# Boron485.net
KiCad netlist of a schematic drawn in EAGLE
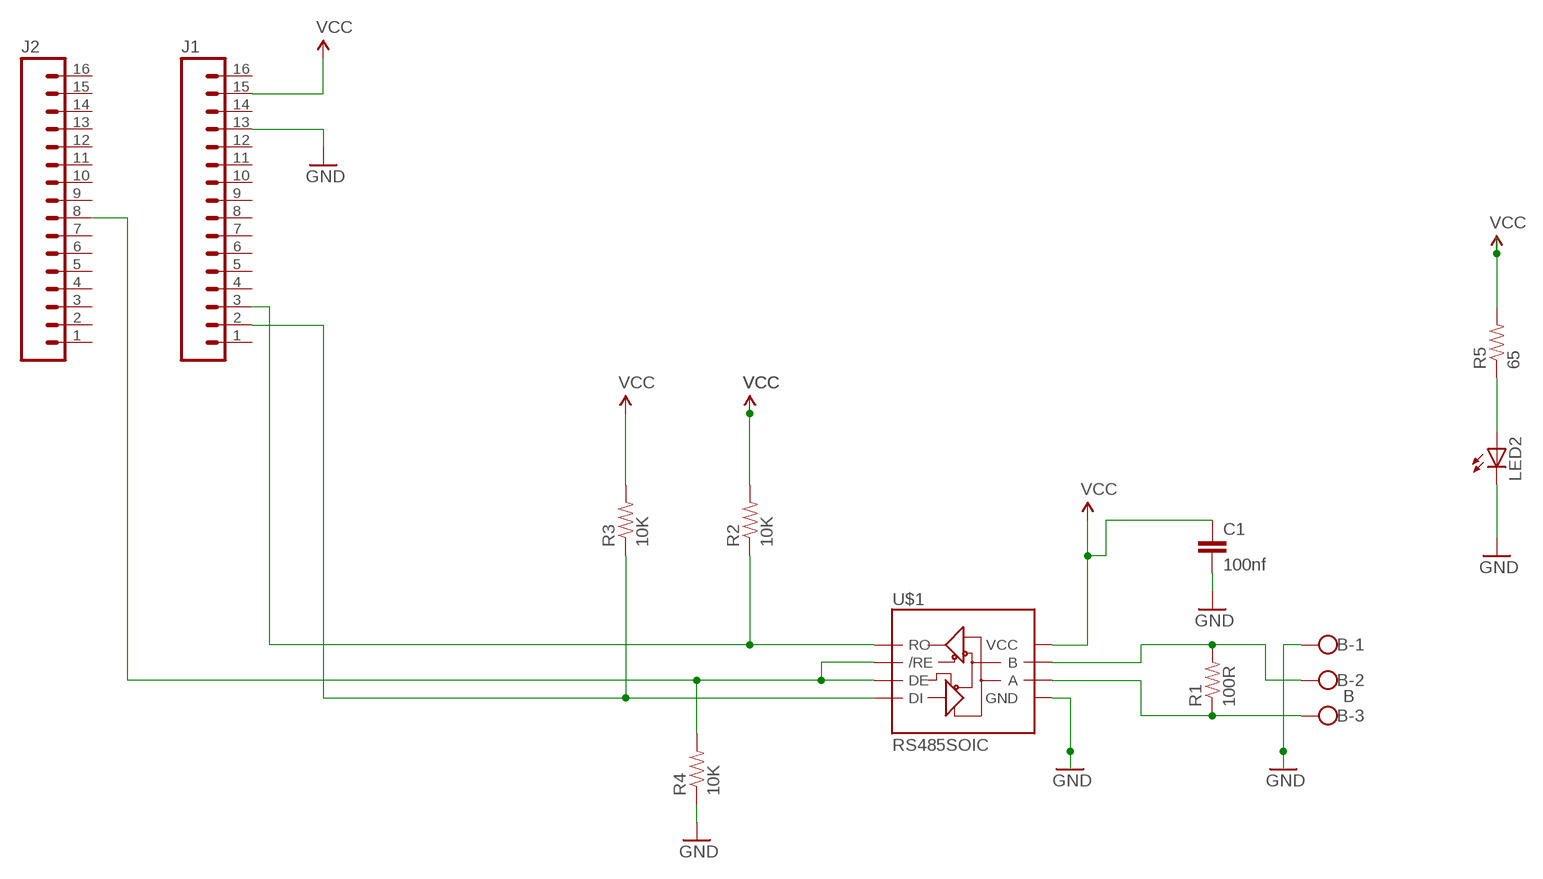
[diagram p0: schematic, sheet 1]

(export (version "E")
  (design (tool "Eeschema 10.0.6"))
  (components
    (comp (ref "B")
      (value "B")
      (footprint "eagle-import:W237-103")
      (fields (field (name "MPN") "237-103"))
      (libsource (lib "eagle-import") (part "W237-103"))
    )
    (comp (ref "C1")
      (value "100nf")
      (footprint "eagle-import:C0603")
      (libsource (lib "eagle-import") (part "C-EUC0603"))
    )
    (comp (ref "J1")
      (value "M16PTH")
      (footprint "eagle-import:1X16")
      (libsource (lib "eagle-import") (part "M16PTH"))
    )
    (comp (ref "J2")
      (value "M16PTH")
      (footprint "eagle-import:1X16")
      (libsource (lib "eagle-import") (part "M16PTH"))
    )
    (comp (ref "LED2")
      (value "LED_E")
      (footprint "eagle-import:LED_1206")
      (libsource (lib "eagle-import") (part "LED_E"))
    )
    (comp (ref "R1")
      (value "100R")
      (footprint "eagle-import:0603-RES")
      (libsource (lib "eagle-import") (part "RESISTOR0603-RES"))
    )
    (comp (ref "R2")
      (value "10K")
      (footprint "eagle-import:0603-RES")
      (libsource (lib "eagle-import") (part "RESISTOR0603-RES"))
    )
    (comp (ref "R3")
      (value "10K")
      (footprint "eagle-import:0603-RES")
      (libsource (lib "eagle-import") (part "RESISTOR0603-RES"))
    )
    (comp (ref "R4")
      (value "10K")
      (footprint "eagle-import:0603-RES")
      (libsource (lib "eagle-import") (part "RESISTOR0603-RES"))
    )
    (comp (ref "R5")
      (value "65")
      (footprint "eagle-import:0603-RES")
      (libsource (lib "eagle-import") (part "RESISTOR0603-RES"))
    )
    (comp (ref "U$1")
      (value "RS485SOIC")
      (footprint "eagle-import:SO08")
      (libsource (lib "eagle-import") (part "RS485SOIC"))
    )
  )
  (nets
    (net (code "1") (name "GND") (class "Default")
      (node (ref "B") (pin "1") (pinfunction "KL_1") (pintype "passive"))
      (node (ref "C1") (pin "2") (pinfunction "2_2") (pintype "passive"))
      (node (ref "J1") (pin "13") (pinfunction "13_13") (pintype "passive"))
      (node (ref "LED2") (pin "C") (pinfunction "C_C") (pintype "passive"))
      (node (ref "R4") (pin "1") (pinfunction "1_1") (pintype "passive"))
      (node (ref "U$1") (pin "5") (pinfunction "GND_5") (pintype "bidirectional"))
    )
    (net (code "2") (name "Net-(BB-KL)") (class "Default")
      (node (ref "B") (pin "2") (pinfunction "KL_2") (pintype "passive"))
      (node (ref "R1") (pin "2") (pinfunction "2_2") (pintype "passive"))
      (node (ref "U$1") (pin "7") (pinfunction "B_7") (pintype "bidirectional"))
    )
    (net (code "3") (name "Net-(BC-KL)") (class "Default")
      (node (ref "B") (pin "3") (pinfunction "KL_3") (pintype "passive"))
      (node (ref "R1") (pin "1") (pinfunction "1_1") (pintype "passive"))
      (node (ref "U$1") (pin "6") (pinfunction "A_6") (pintype "bidirectional"))
    )
    (net (code "4") (name "Net-(LED2-PadA)") (class "Default")
      (node (ref "LED2") (pin "A") (pinfunction "A_A") (pintype "passive"))
      (node (ref "R5") (pin "1") (pinfunction "1_1") (pintype "passive"))
    )
    (net (code "5") (name "Net-(U$1-DE)") (class "Default")
      (node (ref "J2") (pin "8") (pinfunction "8_8") (pintype "passive"))
      (node (ref "R4") (pin "2") (pinfunction "2_2") (pintype "passive"))
      (node (ref "U$1") (pin "2") (pinfunction "/RE_2") (pintype "bidirectional"))
      (node (ref "U$1") (pin "3") (pinfunction "DE_3") (pintype "bidirectional"))
    )
    (net (code "6") (name "Net-(U$1-DI)") (class "Default")
      (node (ref "J1") (pin "2") (pinfunction "2_2") (pintype "passive"))
      (node (ref "R3") (pin "1") (pinfunction "1_1") (pintype "passive"))
      (node (ref "U$1") (pin "4") (pinfunction "DI_4") (pintype "bidirectional"))
    )
    (net (code "7") (name "Net-(U$1-RO)") (class "Default")
      (node (ref "J1") (pin "3") (pinfunction "3_3") (pintype "passive"))
      (node (ref "R2") (pin "1") (pinfunction "1_1") (pintype "passive"))
      (node (ref "U$1") (pin "1") (pinfunction "RO_1") (pintype "bidirectional"))
    )
    (net (code "8") (name "VCC") (class "Default")
      (node (ref "C1") (pin "1") (pinfunction "1_1") (pintype "passive"))
      (node (ref "J1") (pin "15") (pinfunction "15_15") (pintype "passive"))
      (node (ref "R2") (pin "2") (pinfunction "2_2") (pintype "passive"))
      (node (ref "R3") (pin "2") (pinfunction "2_2") (pintype "passive"))
      (node (ref "R5") (pin "2") (pinfunction "2_2") (pintype "passive"))
      (node (ref "U$1") (pin "8") (pinfunction "VCC_8") (pintype "bidirectional"))
    )
    (net (code "9") (name "unconnected-(J1-Pad1)") (class "Default")
      (node (ref "J1") (pin "1") (pinfunction "1_1") (pintype "passive"))
    )
    (net (code "10") (name "unconnected-(J1-Pad4)") (class "Default")
      (node (ref "J1") (pin "4") (pinfunction "4_4") (pintype "passive"))
    )
    (net (code "11") (name "unconnected-(J1-Pad5)") (class "Default")
      (node (ref "J1") (pin "5") (pinfunction "5_5") (pintype "passive"))
    )
    (net (code "12") (name "unconnected-(J1-Pad6)") (class "Default")
      (node (ref "J1") (pin "6") (pinfunction "6_6") (pintype "passive"))
    )
    (net (code "13") (name "unconnected-(J1-Pad7)") (class "Default")
      (node (ref "J1") (pin "7") (pinfunction "7_7") (pintype "passive"))
    )
    (net (code "14") (name "unconnected-(J1-Pad8)") (class "Default")
      (node (ref "J1") (pin "8") (pinfunction "8_8") (pintype "passive"))
    )
    (net (code "15") (name "unconnected-(J1-Pad9)") (class "Default")
      (node (ref "J1") (pin "9") (pinfunction "9_9") (pintype "passive"))
    )
    (net (code "16") (name "unconnected-(J1-Pad10)") (class "Default")
      (node (ref "J1") (pin "10") (pinfunction "10_10") (pintype "passive"))
    )
    (net (code "17") (name "unconnected-(J1-Pad11)") (class "Default")
      (node (ref "J1") (pin "11") (pinfunction "11_11") (pintype "passive"))
    )
    (net (code "18") (name "unconnected-(J1-Pad12)") (class "Default")
      (node (ref "J1") (pin "12") (pinfunction "12_12") (pintype "passive"))
    )
    (net (code "19") (name "unconnected-(J1-Pad14)") (class "Default")
      (node (ref "J1") (pin "14") (pinfunction "14_14") (pintype "passive"))
    )
    (net (code "20") (name "unconnected-(J1-Pad16)") (class "Default")
      (node (ref "J1") (pin "16") (pinfunction "16_16") (pintype "passive"))
    )
    (net (code "21") (name "unconnected-(J2-Pad1)") (class "Default")
      (node (ref "J2") (pin "1") (pinfunction "1_1") (pintype "passive"))
    )
    (net (code "22") (name "unconnected-(J2-Pad2)") (class "Default")
      (node (ref "J2") (pin "2") (pinfunction "2_2") (pintype "passive"))
    )
    (net (code "23") (name "unconnected-(J2-Pad3)") (class "Default")
      (node (ref "J2") (pin "3") (pinfunction "3_3") (pintype "passive"))
    )
    (net (code "24") (name "unconnected-(J2-Pad4)") (class "Default")
      (node (ref "J2") (pin "4") (pinfunction "4_4") (pintype "passive"))
    )
    (net (code "25") (name "unconnected-(J2-Pad5)") (class "Default")
      (node (ref "J2") (pin "5") (pinfunction "5_5") (pintype "passive"))
    )
    (net (code "26") (name "unconnected-(J2-Pad6)") (class "Default")
      (node (ref "J2") (pin "6") (pinfunction "6_6") (pintype "passive"))
    )
    (net (code "27") (name "unconnected-(J2-Pad7)") (class "Default")
      (node (ref "J2") (pin "7") (pinfunction "7_7") (pintype "passive"))
    )
    (net (code "28") (name "unconnected-(J2-Pad9)") (class "Default")
      (node (ref "J2") (pin "9") (pinfunction "9_9") (pintype "passive"))
    )
    (net (code "29") (name "unconnected-(J2-Pad10)") (class "Default")
      (node (ref "J2") (pin "10") (pinfunction "10_10") (pintype "passive"))
    )
    (net (code "30") (name "unconnected-(J2-Pad11)") (class "Default")
      (node (ref "J2") (pin "11") (pinfunction "11_11") (pintype "passive"))
    )
    (net (code "31") (name "unconnected-(J2-Pad12)") (class "Default")
      (node (ref "J2") (pin "12") (pinfunction "12_12") (pintype "passive"))
    )
    (net (code "32") (name "unconnected-(J2-Pad13)") (class "Default")
      (node (ref "J2") (pin "13") (pinfunction "13_13") (pintype "passive"))
    )
    (net (code "33") (name "unconnected-(J2-Pad14)") (class "Default")
      (node (ref "J2") (pin "14") (pinfunction "14_14") (pintype "passive"))
    )
    (net (code "34") (name "unconnected-(J2-Pad15)") (class "Default")
      (node (ref "J2") (pin "15") (pinfunction "15_15") (pintype "passive"))
    )
    (net (code "35") (name "unconnected-(J2-Pad16)") (class "Default")
      (node (ref "J2") (pin "16") (pinfunction "16_16") (pintype "passive"))
    )
  )
)
